# SCH_HackClubCard_2025-02-12.net
KiCad netlist of a schematic drawn in EasyEDA
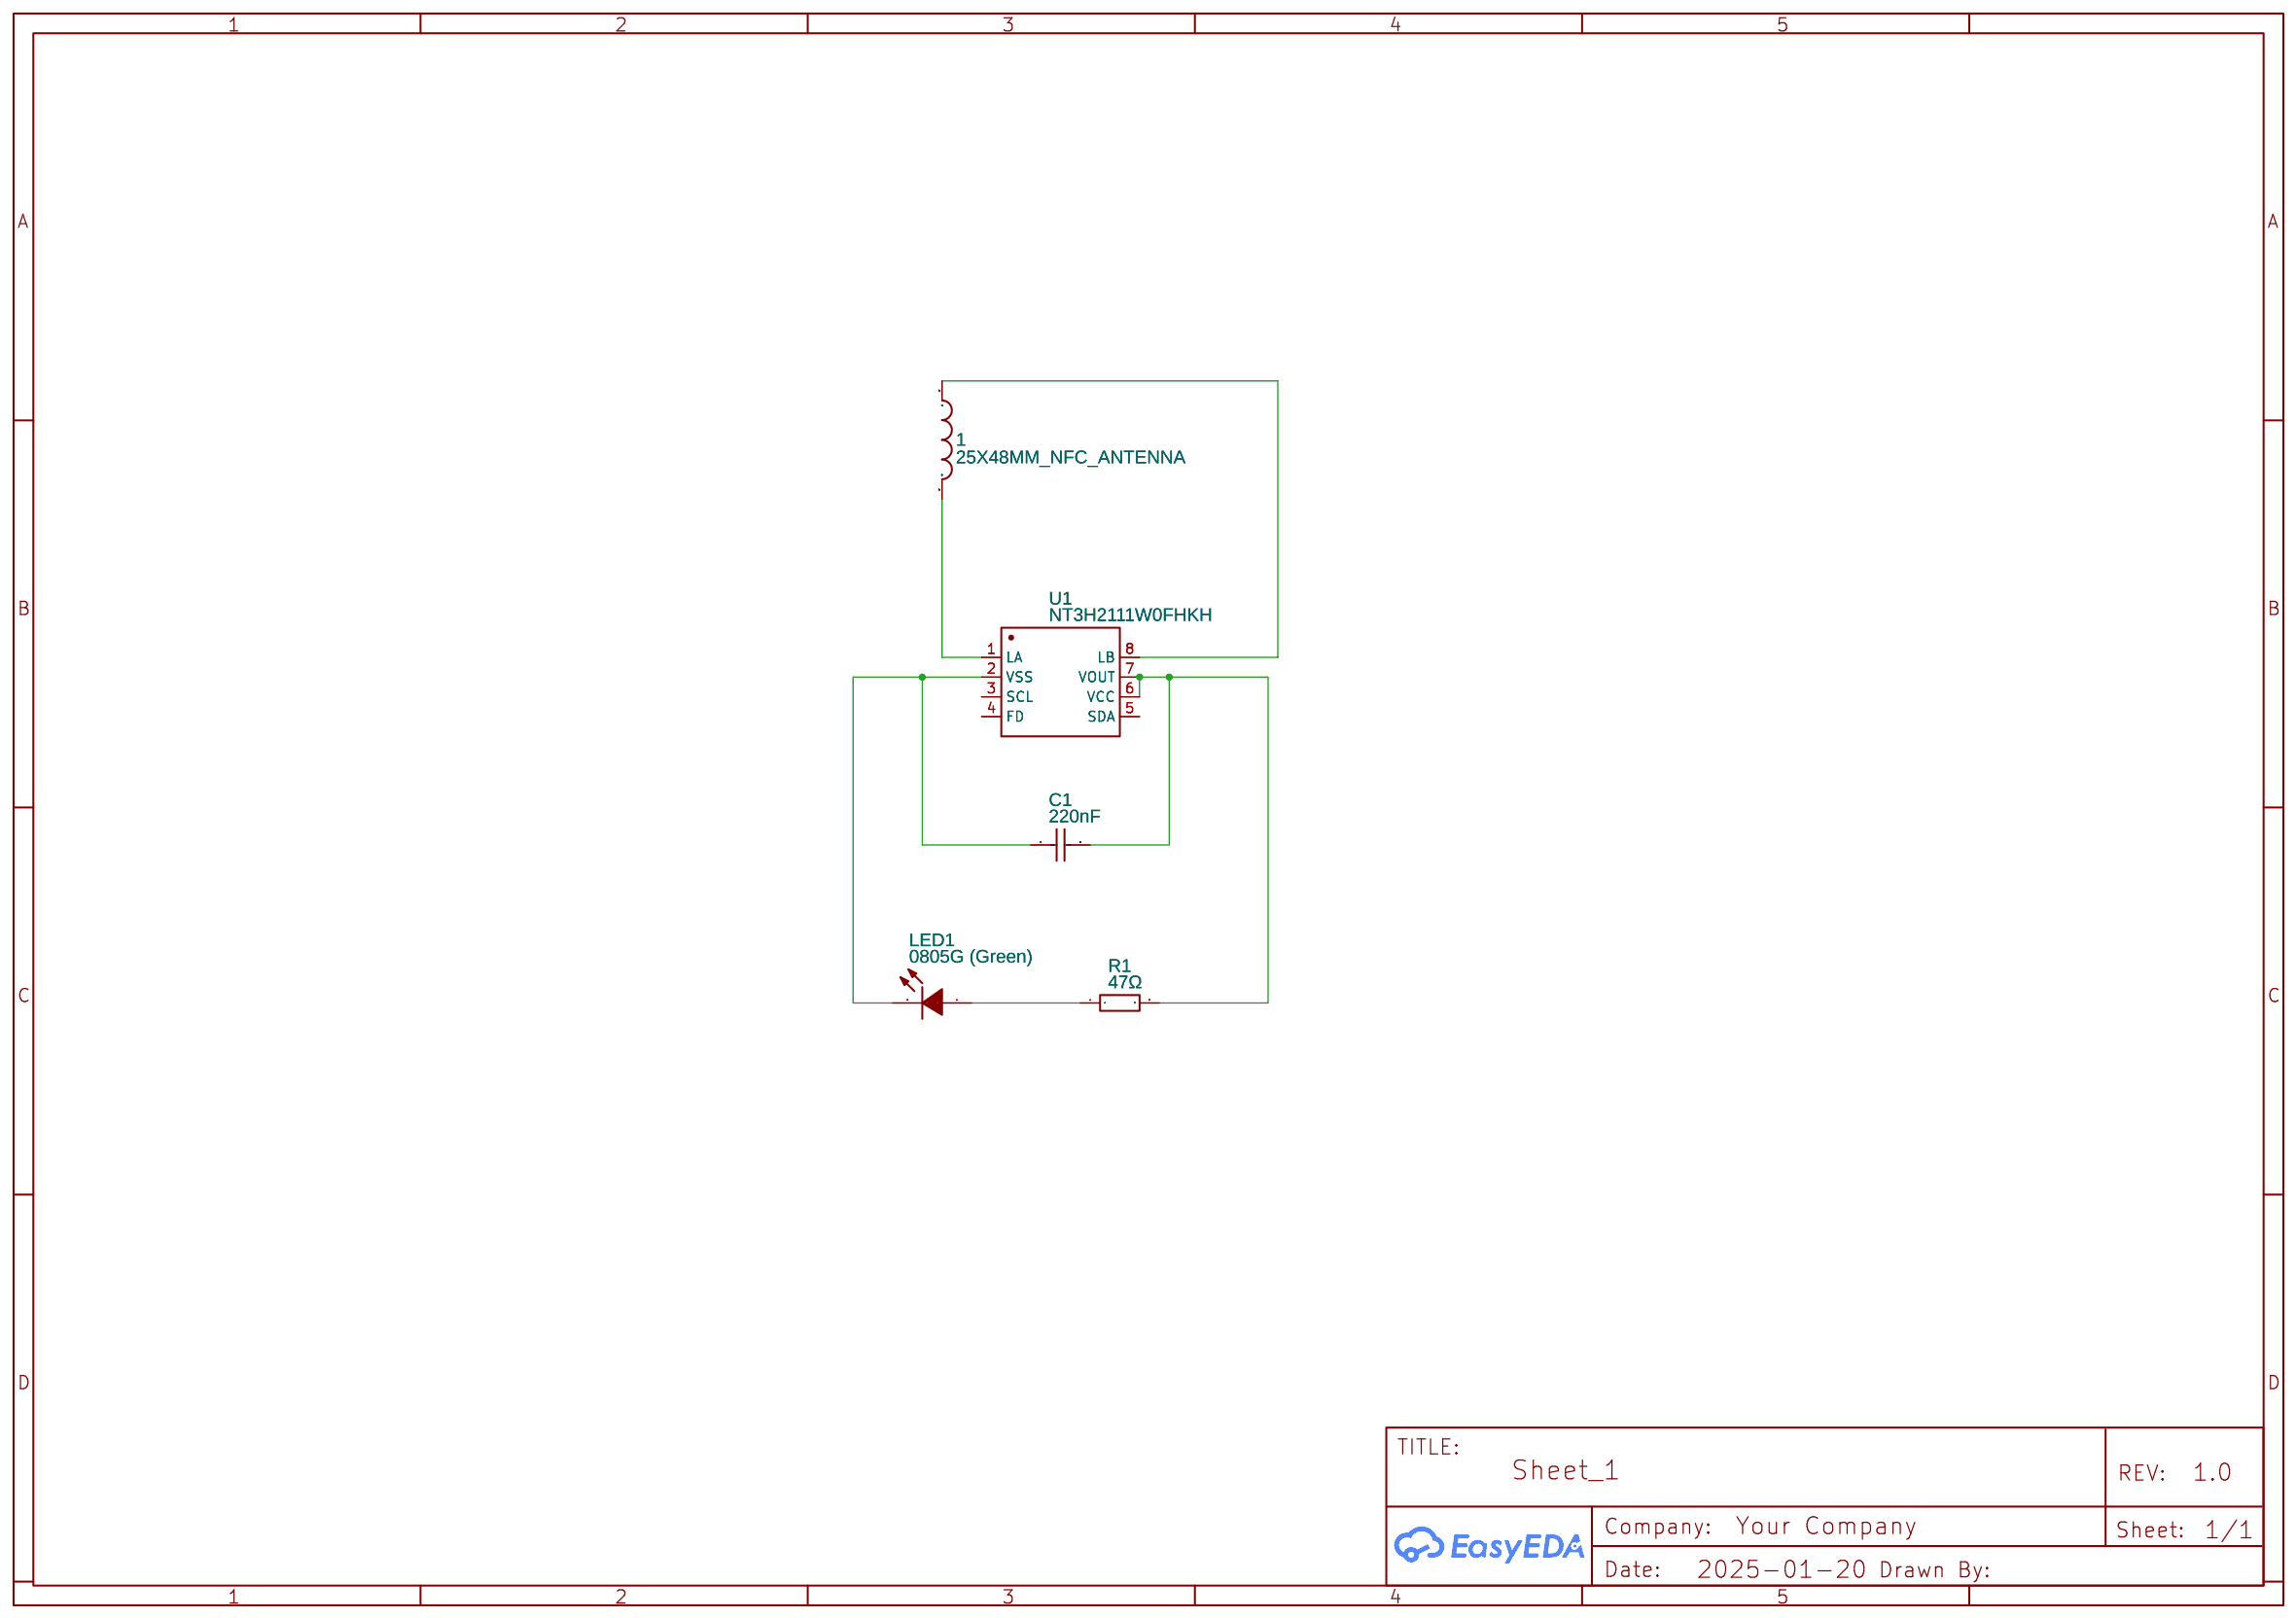
[diagram p0: schematic sheet]

(export (version "E")
  (design (tool "Eeschema 10.0.6"))
  (components
    (comp (ref "1") (value "25X48MM_NFC_ANTENNA") (libsource (lib "") (part "25X48MM_NFC_ANTENNA")))
    (comp (ref "C1")
      (value "220nF")
      (fields
        (field (name "Manufacturer Part") "CL10B224KA8NNNC")
        (field (name "Manufacturer") "SAMSUNG(三星)")
      )
      (libsource (lib "") (part "CL10B224KA8NNNC"))
    )
    (comp (ref "LED1")
      (value "0805G (Green)")
      (fields (field (name "Manufacturer Part") "KT-0805G") (field (name "Manufacturer") "KENTO"))
      (libsource (lib "") (part "0805G (Green)"))
    )
    (comp (ref "R1")
      (value "47Ω")
      (fields
        (field (name "Manufacturer Part") "0603WAF470JT5E")
        (field (name "Manufacturer") "UNI-ROYAL(厚声)")
      )
      (libsource (lib "") (part "0603WAF470JT5E"))
    )
    (comp (ref "U1")
      (value "NT3H2111W0FHKH")
      (fields (field (name "Manufacturer") "NXP(恩智浦)"))
      (libsource (lib "") (part "NT3H2111W0FHKH"))
    )
  )
  (nets
    (net (code "1") (name "Net-(LED1-A)") (class "Default")
      (node (ref "LED1") (pin "1") (pinfunction "A_1") (pintype "unspecified"))
      (node (ref "R1") (pin "1") (pinfunction "1_1") (pintype "input"))
    )
    (net (code "2") (name "Net-(LED1-K)") (class "Default")
      (node (ref "C1") (pin "1") (pinfunction "1_1") (pintype "input"))
      (node (ref "LED1") (pin "2") (pinfunction "K_2") (pintype "unspecified"))
      (node (ref "U1") (pin "2") (pinfunction "VSS_2") (pintype "unspecified"))
    )
    (net (code "3") (name "Net-(U1-LA)") (class "Default")
      (node (ref "1") (pin "P$2") (pinfunction "P$2_P$2") (pintype "bidirectional"))
      (node (ref "U1") (pin "1") (pinfunction "LA_1") (pintype "unspecified"))
    )
    (net (code "4") (name "Net-(U1-LB)") (class "Default")
      (node (ref "1") (pin "P$1") (pinfunction "P$1_P$1") (pintype "bidirectional"))
      (node (ref "U1") (pin "8") (pinfunction "LB_8") (pintype "unspecified"))
    )
    (net (code "5") (name "Net-(U1-VCC)") (class "Default")
      (node (ref "C1") (pin "2") (pinfunction "2_2") (pintype "input"))
      (node (ref "R1") (pin "2") (pinfunction "2_2") (pintype "input"))
      (node (ref "U1") (pin "6") (pinfunction "VCC_6") (pintype "unspecified"))
      (node (ref "U1") (pin "7") (pinfunction "VOUT_7") (pintype "unspecified"))
    )
    (net (code "6") (name "unconnected-(U1-FD-Pad4)") (class "Default")
      (node (ref "U1") (pin "4") (pinfunction "FD_4") (pintype "unspecified"))
    )
    (net (code "7") (name "unconnected-(U1-SCL-Pad3)") (class "Default")
      (node (ref "U1") (pin "3") (pinfunction "SCL_3") (pintype "unspecified"))
    )
    (net (code "8") (name "unconnected-(U1-SDA-Pad5)") (class "Default")
      (node (ref "U1") (pin "5") (pinfunction "SDA_5") (pintype "unspecified"))
    )
  )
)
